# Maker_Faire_Machine_Panel4_P1_dont_use_p.net
KiCad netlist of a schematic drawn in EAGLE
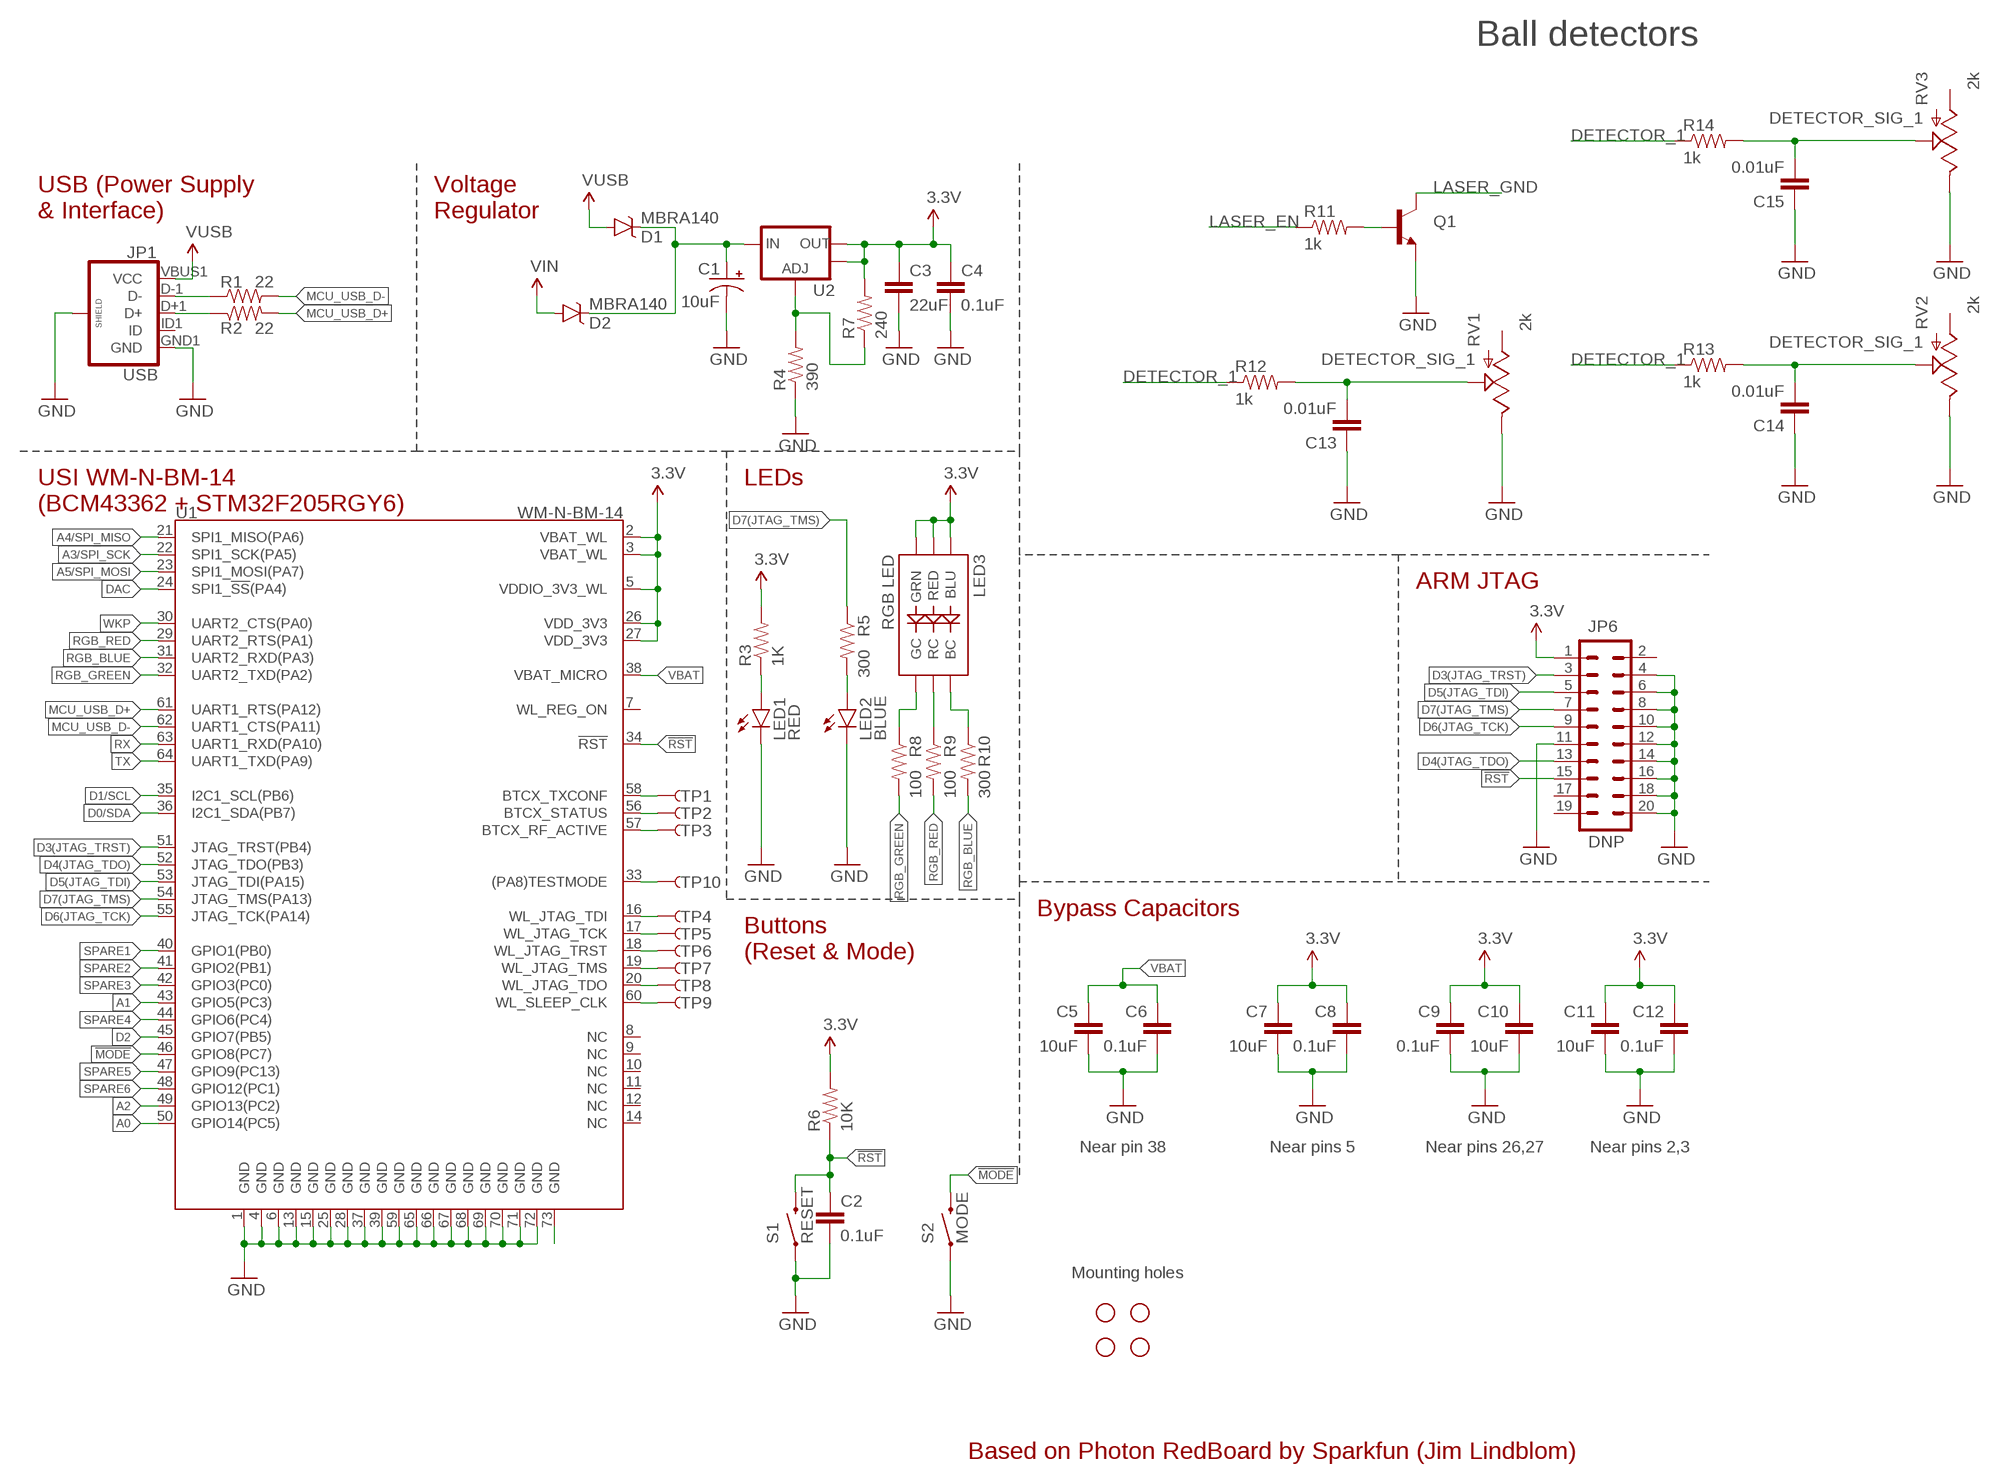
[diagram p0: schematic, sheet 1]

(export (version "E")
  (design (tool "Eeschema 10.0.6"))
  (components
    (comp (ref "C1")
      (value "10uF")
      (footprint "eagle-import:EIA3216")
      (libsource (lib "eagle-import") (part "10UF-16V-10%(TANT)"))
    )
    (comp (ref "C2")
      (value "0.1uF")
      (footprint "eagle-import:0603-CAP")
      (libsource (lib "eagle-import") (part "0.1UF-25V(+80/-20%)(0603)"))
    )
    (comp (ref "C3")
      (value "22uF")
      (footprint "eagle-import:0805")
      (libsource (lib "eagle-import") (part "22UF-6.3V-20%(0805)"))
    )
    (comp (ref "C4")
      (value "0.1uF")
      (footprint "eagle-import:0603-CAP")
      (libsource (lib "eagle-import") (part "0.1UF-25V(+80/-20%)(0603)"))
    )
    (comp (ref "C5")
      (value "10uF")
      (footprint "eagle-import:0603-CAP")
      (libsource (lib "eagle-import") (part "10UF-6.3V-20%(0603)"))
    )
    (comp (ref "C6")
      (value "0.1uF")
      (footprint "eagle-import:0603-CAP")
      (libsource (lib "eagle-import") (part "0.1UF-25V(+80/-20%)(0603)"))
    )
    (comp (ref "C7")
      (value "10uF")
      (footprint "eagle-import:0603-CAP")
      (libsource (lib "eagle-import") (part "10UF-6.3V-20%(0603)"))
    )
    (comp (ref "C8")
      (value "0.1uF")
      (footprint "eagle-import:0603-CAP")
      (libsource (lib "eagle-import") (part "0.1UF-25V(+80/-20%)(0603)"))
    )
    (comp (ref "C9")
      (value "0.1uF")
      (footprint "eagle-import:0603-CAP")
      (libsource (lib "eagle-import") (part "0.1UF-25V(+80/-20%)(0603)"))
    )
    (comp (ref "C10")
      (value "10uF")
      (footprint "eagle-import:0603-CAP")
      (libsource (lib "eagle-import") (part "10UF-6.3V-20%(0603)"))
    )
    (comp (ref "C11")
      (value "10uF")
      (footprint "eagle-import:0603-CAP")
      (libsource (lib "eagle-import") (part "10UF-6.3V-20%(0603)"))
    )
    (comp (ref "C12")
      (value "0.1uF")
      (footprint "eagle-import:0603-CAP")
      (libsource (lib "eagle-import") (part "0.1UF-25V(+80/-20%)(0603)"))
    )
    (comp (ref "C13")
      (value "0.01uF")
      (footprint "eagle-import:1206")
      (fields (field (name "PARTNO") "12065C103KAT2A"))
      (libsource (lib "eagle-import") (part "CAP1206"))
    )
    (comp (ref "C14")
      (value "0.01uF")
      (footprint "eagle-import:1206")
      (fields (field (name "PARTNO") "12065C103KAT2A"))
      (libsource (lib "eagle-import") (part "CAP1206"))
    )
    (comp (ref "C15")
      (value "0.01uF")
      (footprint "eagle-import:1206")
      (fields (field (name "PARTNO") "12065C103KAT2A"))
      (libsource (lib "eagle-import") (part "CAP1206"))
    )
    (comp (ref "D1")
      (value "MBRA140")
      (footprint "eagle-import:SMA-DIODE")
      (libsource (lib "eagle-import") (part "DIODE-SCHOTTKY-MBRA140"))
    )
    (comp (ref "D2")
      (value "MBRA140")
      (footprint "eagle-import:SMA-DIODE")
      (libsource (lib "eagle-import") (part "DIODE-SCHOTTKY-MBRA140"))
    )
    (comp (ref "JP1")
      (value "USB")
      (footprint "eagle-import:USB-B-MICRO-SMD_V03")
      (libsource (lib "eagle-import") (part "USB_MICROB_PLUGCONN-11752"))
    )
    (comp (ref "JP6")
      (value "DNP")
      (footprint "eagle-import:2X10")
      (libsource (lib "eagle-import") (part "M10X2"))
    )
    (comp (ref "LED1")
      (value "RED")
      (footprint "eagle-import:LED-1206")
      (libsource (lib "eagle-import") (part "LED-RED1206"))
    )
    (comp (ref "LED2")
      (value "BLUE")
      (footprint "eagle-import:LED-1206")
      (libsource (lib "eagle-import") (part "LED-BLUE1206"))
    )
    (comp (ref "LED3")
      (value "RGB LED")
      (footprint "eagle-import:PLCC-6-LED")
      (libsource (lib "eagle-import") (part "LED-TRICOLOR-NO-COMPLCC-6-SMD"))
    )
    (comp (ref "Q1")
      (value "TRANSISTOR_NPNSOT89")
      (footprint "eagle-import:SOT89")
      (fields (field (name "PARTNO") "PN2222ABU"))
      (libsource (lib "eagle-import") (part "TRANSISTOR_NPNSOT89"))
    )
    (comp (ref "R1")
      (value "22")
      (footprint "eagle-import:0603-RES")
      (libsource (lib "eagle-import") (part "22OHM1/10W1%(0603)"))
    )
    (comp (ref "R2")
      (value "22")
      (footprint "eagle-import:0603-RES")
      (libsource (lib "eagle-import") (part "22OHM1/10W1%(0603)"))
    )
    (comp (ref "R3")
      (value "1K")
      (footprint "eagle-import:0603-RES")
      (libsource (lib "eagle-import") (part "1KOHM-1/10W-1%(0603)"))
    )
    (comp (ref "R4")
      (value "390")
      (footprint "eagle-import:0603-RES")
      (libsource (lib "eagle-import") (part "390OHM1/10W1%(0603)"))
    )
    (comp (ref "R5")
      (value "300")
      (footprint "eagle-import:0603-RES")
      (libsource (lib "eagle-import") (part "300OHM-1/10W-1%(0603)"))
    )
    (comp (ref "R6")
      (value "10K")
      (footprint "eagle-import:0603-RES")
      (libsource (lib "eagle-import") (part "10KOHM-1/10W-1%(0603)0603"))
    )
    (comp (ref "R7")
      (value "240")
      (footprint "eagle-import:0603-RES")
      (libsource (lib "eagle-import") (part "240OHM1/10W1%(0603)"))
    )
    (comp (ref "R8")
      (value "100")
      (footprint "eagle-import:0603-RES")
      (libsource (lib "eagle-import") (part "100OHM-1/10W-1%(0603)"))
    )
    (comp (ref "R9")
      (value "100")
      (footprint "eagle-import:0603-RES")
      (libsource (lib "eagle-import") (part "100OHM-1/10W-1%(0603)"))
    )
    (comp (ref "R10")
      (value "300")
      (footprint "eagle-import:0603-RES")
      (libsource (lib "eagle-import") (part "300OHM-1/10W-1%(0603)"))
    )
    (comp (ref "R11")
      (value "1k")
      (footprint "eagle-import:1206")
      (fields (field (name "PARTNO") "ERJ-8ENF1001V"))
      (libsource (lib "eagle-import") (part "RESISTOR1206"))
    )
    (comp (ref "R12")
      (value "1k")
      (footprint "eagle-import:1206")
      (fields (field (name "PARTNO") "ERJ-8ENF1001V"))
      (libsource (lib "eagle-import") (part "RESISTOR1206"))
    )
    (comp (ref "R13")
      (value "1k")
      (footprint "eagle-import:1206")
      (fields (field (name "PARTNO") "ERJ-8ENF1001V"))
      (libsource (lib "eagle-import") (part "RESISTOR1206"))
    )
    (comp (ref "R14")
      (value "1k")
      (footprint "eagle-import:1206")
      (fields (field (name "PARTNO") "ERJ-8ENF1001V"))
      (libsource (lib "eagle-import") (part "RESISTOR1206"))
    )
    (comp (ref "RV1")
      (value "2k")
      (footprint "eagle-import:3362U")
      (fields (field (name "PARTNO") "3362U-1-202LF"))
      (libsource (lib "eagle-import") (part "POT100K_3362U"))
    )
    (comp (ref "RV2")
      (value "2k")
      (footprint "eagle-import:3362U")
      (fields (field (name "PARTNO") "3362U-1-202LF"))
      (libsource (lib "eagle-import") (part "POT100K_3362U"))
    )
    (comp (ref "RV3")
      (value "2k")
      (footprint "eagle-import:3362U")
      (fields (field (name "PARTNO") "3362U-1-202LF"))
      (libsource (lib "eagle-import") (part "POT100K_3362U"))
    )
    (comp (ref "S1")
      (value "RESET")
      (footprint "eagle-import:TACTILE-PTH")
      (libsource (lib "eagle-import") (part "SWITCH-MOMENTARY-2PTH"))
    )
    (comp (ref "S2")
      (value "MODE")
      (footprint "eagle-import:TACTILE-PTH")
      (libsource (lib "eagle-import") (part "SWITCH-MOMENTARY-2PTH"))
    )
    (comp (ref "STANDOFF1")
      (value "STAND-OFF")
      (footprint "eagle-import:STAND-OFF")
      (libsource (lib "eagle-import") (part "STAND-OFF"))
    )
    (comp (ref "STANDOFF2")
      (value "STAND-OFF")
      (footprint "eagle-import:STAND-OFF")
      (libsource (lib "eagle-import") (part "STAND-OFF"))
    )
    (comp (ref "STANDOFF3")
      (value "STAND-OFF")
      (footprint "eagle-import:STAND-OFF")
      (libsource (lib "eagle-import") (part "STAND-OFF"))
    )
    (comp (ref "STANDOFF4")
      (value "STAND-OFF")
      (footprint "eagle-import:STAND-OFF")
      (libsource (lib "eagle-import") (part "STAND-OFF"))
    )
    (comp (ref "TP1")
      (value "TEST-POINTTP_15TH_THRU")
      (footprint "eagle-import:TP_15TH")
      (libsource (lib "eagle-import") (part "TEST-POINTTP_15TH_THRU"))
    )
    (comp (ref "TP2")
      (value "TEST-POINTTP_15TH_THRU")
      (footprint "eagle-import:TP_15TH")
      (libsource (lib "eagle-import") (part "TEST-POINTTP_15TH_THRU"))
    )
    (comp (ref "TP3")
      (value "TEST-POINTTP_15TH_THRU")
      (footprint "eagle-import:TP_15TH")
      (libsource (lib "eagle-import") (part "TEST-POINTTP_15TH_THRU"))
    )
    (comp (ref "TP4")
      (value "TEST-POINTTP_15TH_THRU")
      (footprint "eagle-import:TP_15TH")
      (libsource (lib "eagle-import") (part "TEST-POINTTP_15TH_THRU"))
    )
    (comp (ref "TP5")
      (value "TEST-POINTTP_15TH_THRU")
      (footprint "eagle-import:TP_15TH")
      (libsource (lib "eagle-import") (part "TEST-POINTTP_15TH_THRU"))
    )
    (comp (ref "TP6")
      (value "TEST-POINTTP_15TH_THRU")
      (footprint "eagle-import:TP_15TH")
      (libsource (lib "eagle-import") (part "TEST-POINTTP_15TH_THRU"))
    )
    (comp (ref "TP7")
      (value "TEST-POINTTP_15TH_THRU")
      (footprint "eagle-import:TP_15TH")
      (libsource (lib "eagle-import") (part "TEST-POINTTP_15TH_THRU"))
    )
    (comp (ref "TP8")
      (value "TEST-POINTTP_15TH_THRU")
      (footprint "eagle-import:TP_15TH")
      (libsource (lib "eagle-import") (part "TEST-POINTTP_15TH_THRU"))
    )
    (comp (ref "TP9")
      (value "TEST-POINTTP_15TH_THRU")
      (footprint "eagle-import:TP_15TH")
      (libsource (lib "eagle-import") (part "TEST-POINTTP_15TH_THRU"))
    )
    (comp (ref "TP10")
      (value "TEST-POINTTP_15TH_THRU")
      (footprint "eagle-import:TP_15TH")
      (libsource (lib "eagle-import") (part "TEST-POINTTP_15TH_THRU"))
    )
    (comp (ref "U1")
      (value "WM-N-BM-14")
      (footprint "eagle-import:WM-N-BM-14")
      (libsource (lib "eagle-import") (part "WM-N-BM-14"))
    )
    (comp (ref "U2")
      (value "V_REG_LM1117SOT223")
      (footprint "eagle-import:SOT223")
      (libsource (lib "eagle-import") (part "V_REG_LM1117SOT223"))
    )
  )
  (nets
    (net (code "1") (name "/DETECTOR_1") (class "Default")
      (node (ref "R12") (pin "1") (pinfunction "1_1") (pintype "passive"))
      (node (ref "R13") (pin "1") (pinfunction "1_1") (pintype "passive"))
      (node (ref "R14") (pin "1") (pinfunction "1_1") (pintype "passive"))
    )
    (net (code "2") (name "/DETECTOR_SIG_1") (class "Default")
      (node (ref "C13") (pin "2") (pinfunction "2_2") (pintype "passive"))
      (node (ref "C14") (pin "2") (pinfunction "2_2") (pintype "passive"))
      (node (ref "C15") (pin "2") (pinfunction "2_2") (pintype "passive"))
      (node (ref "R12") (pin "2") (pinfunction "2_2") (pintype "passive"))
      (node (ref "R13") (pin "2") (pinfunction "2_2") (pintype "passive"))
      (node (ref "R14") (pin "2") (pinfunction "2_2") (pintype "passive"))
      (node (ref "RV1") (pin "P$2") (pinfunction "S_P$2") (pintype "passive"))
      (node (ref "RV2") (pin "P$2") (pinfunction "S_P$2") (pintype "passive"))
      (node (ref "RV3") (pin "P$2") (pinfunction "S_P$2") (pintype "passive"))
    )
    (net (code "3") (name "/LASER_EN") (class "Default")
      (node (ref "R11") (pin "1") (pinfunction "1_1") (pintype "passive"))
    )
    (net (code "4") (name "/LASER_GND") (class "Default")
      (node (ref "Q1") (pin "2") (pinfunction "C_2") (pintype "passive"))
    )
    (net (code "5") (name "/~{MODE}") (class "Default")
      (node (ref "S2") (pin "3") (pinfunction "2_3") (pintype "passive"))
      (node (ref "U1") (pin "46") (pinfunction "GPIO8(PC7)_46") (pintype "bidirectional"))
    )
    (net (code "6") (name "/~{RST}") (class "Default")
      (node (ref "C2") (pin "1") (pinfunction "1_1") (pintype "passive"))
      (node (ref "JP6") (pin "15") (pinfunction "15_15") (pintype "passive"))
      (node (ref "R6") (pin "1") (pinfunction "1_1") (pintype "passive"))
      (node (ref "S1") (pin "3") (pinfunction "2_3") (pintype "passive"))
      (node (ref "U1") (pin "34") (pinfunction "~{RST}_34") (pintype "bidirectional"))
    )
    (net (code "7") (name "3.3V") (class "Default")
      (node (ref "C10") (pin "1") (pinfunction "1_1") (pintype "passive"))
      (node (ref "C11") (pin "1") (pinfunction "1_1") (pintype "passive"))
      (node (ref "C12") (pin "1") (pinfunction "1_1") (pintype "passive"))
      (node (ref "C3") (pin "1") (pinfunction "1_1") (pintype "passive"))
      (node (ref "C4") (pin "1") (pinfunction "1_1") (pintype "passive"))
      (node (ref "C7") (pin "1") (pinfunction "1_1") (pintype "passive"))
      (node (ref "C8") (pin "1") (pinfunction "1_1") (pintype "passive"))
      (node (ref "C9") (pin "1") (pinfunction "1_1") (pintype "passive"))
      (node (ref "JP6") (pin "1") (pinfunction "1_1") (pintype "passive"))
      (node (ref "LED3") (pin "AB") (pinfunction "BLU_AB") (pintype "bidirectional"))
      (node (ref "LED3") (pin "AG") (pinfunction "GRN_AG") (pintype "bidirectional"))
      (node (ref "LED3") (pin "AR") (pinfunction "RED_AR") (pintype "bidirectional"))
      (node (ref "R3") (pin "2") (pinfunction "2_2") (pintype "passive"))
      (node (ref "R6") (pin "2") (pinfunction "2_2") (pintype "passive"))
      (node (ref "R7") (pin "2") (pinfunction "2_2") (pintype "passive"))
      (node (ref "U1") (pin "2") (pinfunction "VBAT_WL_2") (pintype "bidirectional"))
      (node (ref "U1") (pin "26") (pinfunction "VDD_3V3_26") (pintype "bidirectional"))
      (node (ref "U1") (pin "27") (pinfunction "VDD_3V3_27") (pintype "bidirectional"))
      (node (ref "U1") (pin "3") (pinfunction "VBAT_WL_3") (pintype "bidirectional"))
      (node (ref "U1") (pin "5") (pinfunction "VDDIO_3V3_WL_5") (pintype "bidirectional"))
      (node (ref "U2") (pin "2") (pinfunction "OUT_2") (pintype "output"))
      (node (ref "U2") (pin "4") (pinfunction "OUT_4") (pintype "output"))
    )
    (net (code "8") (name "A0") (class "Default")
      (node (ref "U1") (pin "50") (pinfunction "GPIO14(PC5)_50") (pintype "bidirectional"))
    )
    (net (code "9") (name "A1") (class "Default")
      (node (ref "U1") (pin "43") (pinfunction "GPIO5(PC3)_43") (pintype "bidirectional"))
    )
    (net (code "10") (name "A2") (class "Default")
      (node (ref "U1") (pin "49") (pinfunction "GPIO13(PC2)_49") (pintype "bidirectional"))
    )
    (net (code "11") (name "A3{slash}SPI_SCK") (class "Default")
      (node (ref "U1") (pin "22") (pinfunction "SPI1_SCK(PA5)_22") (pintype "bidirectional"))
    )
    (net (code "12") (name "A4{slash}SPI_MISO") (class "Default")
      (node (ref "U1") (pin "21") (pinfunction "SPI1_MISO(PA6)_21") (pintype "bidirectional"))
    )
    (net (code "13") (name "A5{slash}SPI_MOSI") (class "Default")
      (node (ref "U1") (pin "23") (pinfunction "SPI1_MOSI(PA7)_23") (pintype "bidirectional"))
    )
    (net (code "14") (name "D0{slash}SDA") (class "Default")
      (node (ref "U1") (pin "36") (pinfunction "I2C1_SDA(PB7)_36") (pintype "bidirectional"))
    )
    (net (code "15") (name "D1{slash}SCL") (class "Default")
      (node (ref "U1") (pin "35") (pinfunction "I2C1_SCL(PB6)_35") (pintype "bidirectional"))
    )
    (net (code "16") (name "D2") (class "Default")
      (node (ref "U1") (pin "45") (pinfunction "GPIO7(PB5)_45") (pintype "bidirectional"))
    )
    (net (code "17") (name "D3(JTAG_TRST)") (class "Default")
      (node (ref "JP6") (pin "3") (pinfunction "3_3") (pintype "passive"))
      (node (ref "U1") (pin "51") (pinfunction "JTAG_TRST(PB4)_51") (pintype "bidirectional"))
    )
    (net (code "18") (name "D4(JTAG_TDO)") (class "Default")
      (node (ref "JP6") (pin "13") (pinfunction "13_13") (pintype "passive"))
      (node (ref "U1") (pin "52") (pinfunction "JTAG_TDO(PB3)_52") (pintype "bidirectional"))
    )
    (net (code "19") (name "D5(JTAG_TDI)") (class "Default")
      (node (ref "JP6") (pin "5") (pinfunction "5_5") (pintype "passive"))
      (node (ref "U1") (pin "53") (pinfunction "JTAG_TDI(PA15)_53") (pintype "bidirectional"))
    )
    (net (code "20") (name "D6(JTAG_TCK)") (class "Default")
      (node (ref "JP6") (pin "9") (pinfunction "9_9") (pintype "passive"))
      (node (ref "U1") (pin "55") (pinfunction "JTAG_TCK(PA14)_55") (pintype "bidirectional"))
    )
    (net (code "21") (name "D7(JTAG_TMS)") (class "Default")
      (node (ref "JP6") (pin "7") (pinfunction "7_7") (pintype "passive"))
      (node (ref "R5") (pin "1") (pinfunction "1_1") (pintype "passive"))
      (node (ref "U1") (pin "54") (pinfunction "JTAG_TMS(PA13)_54") (pintype "bidirectional"))
    )
    (net (code "22") (name "DAC") (class "Default")
      (node (ref "U1") (pin "24") (pinfunction "SPI1_~{SS}(PA4)_24") (pintype "bidirectional"))
    )
    (net (code "23") (name "GND") (class "Default")
      (node (ref "C1") (pin "C") (pinfunction "-_C") (pintype "passive"))
      (node (ref "C10") (pin "2") (pinfunction "2_2") (pintype "passive"))
      (node (ref "C11") (pin "2") (pinfunction "2_2") (pintype "passive"))
      (node (ref "C12") (pin "2") (pinfunction "2_2") (pintype "passive"))
      (node (ref "C13") (pin "1") (pinfunction "1_1") (pintype "passive"))
      (node (ref "C14") (pin "1") (pinfunction "1_1") (pintype "passive"))
      (node (ref "C15") (pin "1") (pinfunction "1_1") (pintype "passive"))
      (node (ref "C2") (pin "2") (pinfunction "2_2") (pintype "passive"))
      (node (ref "C3") (pin "2") (pinfunction "2_2") (pintype "passive"))
      (node (ref "C4") (pin "2") (pinfunction "2_2") (pintype "passive"))
      (node (ref "C5") (pin "2") (pinfunction "2_2") (pintype "passive"))
      (node (ref "C6") (pin "2") (pinfunction "2_2") (pintype "passive"))
      (node (ref "C7") (pin "2") (pinfunction "2_2") (pintype "passive"))
      (node (ref "C8") (pin "2") (pinfunction "2_2") (pintype "passive"))
      (node (ref "C9") (pin "2") (pinfunction "2_2") (pintype "passive"))
      (node (ref "JP1") (pin "GND1") (pinfunction "GND_GND1") (pintype "bidirectional"))
      (node (ref "JP1") (pin "SHIELD1") (pinfunction "SHIELD_SHIELD1") (pintype "bidirectional"))
      (node (ref "JP1") (pin "SHIELD2") (pinfunction "SHIELD_SHIELD2") (pintype "bidirectional"))
      (node (ref "JP1") (pin "SHIELD3") (pinfunction "SHIELD_SHIELD3") (pintype "bidirectional"))
      (node (ref "JP6") (pin "10") (pinfunction "10_10") (pintype "passive"))
      (node (ref "JP6") (pin "11") (pinfunction "11_11") (pintype "passive"))
      (node (ref "JP6") (pin "12") (pinfunction "12_12") (pintype "passive"))
      (node (ref "JP6") (pin "14") (pinfunction "14_14") (pintype "passive"))
      (node (ref "JP6") (pin "16") (pinfunction "16_16") (pintype "passive"))
      (node (ref "JP6") (pin "18") (pinfunction "18_18") (pintype "passive"))
      (node (ref "JP6") (pin "20") (pinfunction "20_20") (pintype "passive"))
      (node (ref "JP6") (pin "4") (pinfunction "4_4") (pintype "passive"))
      (node (ref "JP6") (pin "6") (pinfunction "6_6") (pintype "passive"))
      (node (ref "JP6") (pin "8") (pinfunction "8_8") (pintype "passive"))
      (node (ref "LED1") (pin "C") (pinfunction "C_C") (pintype "passive"))
      (node (ref "LED2") (pin "C") (pinfunction "C_C") (pintype "passive"))
      (node (ref "Q1") (pin "3") (pinfunction "E_3") (pintype "passive"))
      (node (ref "R4") (pin "1") (pinfunction "1_1") (pintype "passive"))
      (node (ref "RV1") (pin "P$1") (pinfunction "E_P$1") (pintype "passive"))
      (node (ref "RV2") (pin "P$1") (pinfunction "E_P$1") (pintype "passive"))
      (node (ref "RV3") (pin "P$1") (pinfunction "E_P$1") (pintype "passive"))
      (node (ref "S1") (pin "1") (pinfunction "1_1") (pintype "passive"))
      (node (ref "S2") (pin "1") (pinfunction "1_1") (pintype "passive"))
      (node (ref "U1") (pin "1") (pinfunction "GND_1") (pintype "bidirectional"))
      (node (ref "U1") (pin "13") (pinfunction "GND_13") (pintype "bidirectional"))
      (node (ref "U1") (pin "15") (pinfunction "GND_15") (pintype "bidirectional"))
      (node (ref "U1") (pin "25") (pinfunction "GND_25") (pintype "bidirectional"))
      (node (ref "U1") (pin "28") (pinfunction "GND_28") (pintype "bidirectional"))
      (node (ref "U1") (pin "37") (pinfunction "GND_37") (pintype "bidirectional"))
      (node (ref "U1") (pin "39") (pinfunction "GND_39") (pintype "bidirectional"))
      (node (ref "U1") (pin "4") (pinfunction "GND_4") (pintype "bidirectional"))
      (node (ref "U1") (pin "59") (pinfunction "GND_59") (pintype "bidirectional"))
      (node (ref "U1") (pin "6") (pinfunction "GND_6") (pintype "bidirectional"))
      (node (ref "U1") (pin "65") (pinfunction "GND_65") (pintype "bidirectional"))
      (node (ref "U1") (pin "66") (pinfunction "GND_66") (pintype "bidirectional"))
      (node (ref "U1") (pin "67") (pinfunction "GND_67") (pintype "bidirectional"))
      (node (ref "U1") (pin "68") (pinfunction "GND_68") (pintype "bidirectional"))
      (node (ref "U1") (pin "69") (pinfunction "GND_69") (pintype "bidirectional"))
      (node (ref "U1") (pin "70") (pinfunction "GND_70") (pintype "bidirectional"))
      (node (ref "U1") (pin "71") (pinfunction "GND_71") (pintype "bidirectional"))
      (node (ref "U1") (pin "72") (pinfunction "GND_72") (pintype "bidirectional"))
    )
    (net (code "24") (name "MCU_USB_D+") (class "Default")
      (node (ref "R2") (pin "2") (pinfunction "2_2") (pintype "passive"))
      (node (ref "U1") (pin "61") (pinfunction "UART1_RTS(PA12)_61") (pintype "bidirectional"))
    )
    (net (code "25") (name "MCU_USB_D-") (class "Default")
      (node (ref "R1") (pin "2") (pinfunction "2_2") (pintype "passive"))
      (node (ref "U1") (pin "62") (pinfunction "UART1_CTS(PA11)_62") (pintype "bidirectional"))
    )
    (net (code "26") (name "Net-(C1-+)") (class "Default")
      (node (ref "C1") (pin "A") (pinfunction "+_A") (pintype "passive"))
      (node (ref "D1") (pin "C") (pinfunction "C_C") (pintype "passive"))
      (node (ref "D2") (pin "C") (pinfunction "C_C") (pintype "passive"))
      (node (ref "U2") (pin "3") (pinfunction "IN_3") (pintype "input"))
    )
    (net (code "27") (name "Net-(JP1-D+)") (class "Default")
      (node (ref "JP1") (pin "D+1") (pinfunction "D+_D+1") (pintype "bidirectional"))
      (node (ref "R2") (pin "1") (pinfunction "1_1") (pintype "passive"))
    )
    (net (code "28") (name "Net-(JP1-D-)") (class "Default")
      (node (ref "JP1") (pin "D-1") (pinfunction "D-_D-1") (pintype "bidirectional"))
      (node (ref "R1") (pin "1") (pinfunction "1_1") (pintype "passive"))
    )
    (net (code "29") (name "Net-(LED1-PadA)") (class "Default")
      (node (ref "LED1") (pin "A") (pinfunction "A_A") (pintype "passive"))
      (node (ref "R3") (pin "1") (pinfunction "1_1") (pintype "passive"))
    )
    (net (code "30") (name "Net-(LED2-PadA)") (class "Default")
      (node (ref "LED2") (pin "A") (pinfunction "A_A") (pintype "passive"))
      (node (ref "R5") (pin "2") (pinfunction "2_2") (pintype "passive"))
    )
    (net (code "31") (name "Net-(LED3-BC)") (class "Default")
      (node (ref "LED3") (pin "CB") (pinfunction "BC_CB") (pintype "bidirectional"))
      (node (ref "R10") (pin "1") (pinfunction "1_1") (pintype "passive"))
    )
    (net (code "32") (name "Net-(LED3-GC)") (class "Default")
      (node (ref "LED3") (pin "CG") (pinfunction "GC_CG") (pintype "bidirectional"))
      (node (ref "R8") (pin "1") (pinfunction "1_1") (pintype "passive"))
    )
    (net (code "33") (name "Net-(LED3-RC)") (class "Default")
      (node (ref "LED3") (pin "CR") (pinfunction "RC_CR") (pintype "bidirectional"))
      (node (ref "R9") (pin "1") (pinfunction "1_1") (pintype "passive"))
    )
    (net (code "34") (name "Net-(Q1-B)") (class "Default")
      (node (ref "Q1") (pin "1") (pinfunction "B_1") (pintype "passive"))
      (node (ref "R11") (pin "2") (pinfunction "2_2") (pintype "passive"))
    )
    (net (code "35") (name "Net-(TP1-1)") (class "Default")
      (node (ref "TP1") (pin "P$1") (pinfunction "1_P$1") (pintype "bidirectional"))
      (node (ref "U1") (pin "58") (pinfunction "BTCX_TXCONF_58") (pintype "bidirectional"))
    )
    (net (code "36") (name "Net-(TP2-1)") (class "Default")
      (node (ref "TP2") (pin "P$1") (pinfunction "1_P$1") (pintype "bidirectional"))
      (node (ref "U1") (pin "56") (pinfunction "BTCX_STATUS_56") (pintype "bidirectional"))
    )
    (net (code "37") (name "Net-(TP3-1)") (class "Default")
      (node (ref "TP3") (pin "P$1") (pinfunction "1_P$1") (pintype "bidirectional"))
      (node (ref "U1") (pin "57") (pinfunction "BTCX_RF_ACTIVE_57") (pintype "bidirectional"))
    )
    (net (code "38") (name "Net-(TP4-1)") (class "Default")
      (node (ref "TP4") (pin "P$1") (pinfunction "1_P$1") (pintype "bidirectional"))
      (node (ref "U1") (pin "16") (pinfunction "WL_JTAG_TDI_16") (pintype "bidirectional"))
    )
    (net (code "39") (name "Net-(TP5-1)") (class "Default")
      (node (ref "TP5") (pin "P$1") (pinfunction "1_P$1") (pintype "bidirectional"))
      (node (ref "U1") (pin "17") (pinfunction "WL_JTAG_TCK_17") (pintype "bidirectional"))
    )
    (net (code "40") (name "Net-(TP6-1)") (class "Default")
      (node (ref "TP6") (pin "P$1") (pinfunction "1_P$1") (pintype "bidirectional"))
      (node (ref "U1") (pin "18") (pinfunction "WL_JTAG_TRST_18") (pintype "bidirectional"))
    )
    (net (code "41") (name "Net-(TP7-1)") (class "Default")
      (node (ref "TP7") (pin "P$1") (pinfunction "1_P$1") (pintype "bidirectional"))
      (node (ref "U1") (pin "19") (pinfunction "WL_JTAG_TMS_19") (pintype "bidirectional"))
    )
    (net (code "42") (name "Net-(TP8-1)") (class "Default")
      (node (ref "TP8") (pin "P$1") (pinfunction "1_P$1") (pintype "bidirectional"))
      (node (ref "U1") (pin "20") (pinfunction "WL_JTAG_TDO_20") (pintype "bidirectional"))
    )
    (net (code "43") (name "Net-(TP9-1)") (class "Default")
      (node (ref "TP9") (pin "P$1") (pinfunction "1_P$1") (pintype "bidirectional"))
      (node (ref "U1") (pin "60") (pinfunction "WL_SLEEP_CLK_60") (pintype "bidirectional"))
    )
    (net (code "44") (name "Net-(TP10-1)") (class "Default")
      (node (ref "TP10") (pin "P$1") (pinfunction "1_P$1") (pintype "bidirectional"))
      (node (ref "U1") (pin "33") (pinfunction "(PA8)TESTMODE_33") (pintype "bidirectional"))
    )
    (net (code "45") (name "Net-(U2-ADJ)") (class "Default")
      (node (ref "R4") (pin "2") (pinfunction "2_2") (pintype "passive"))
      (node (ref "R7") (pin "1") (pinfunction "1_1") (pintype "passive"))
      (node (ref "U2") (pin "1") (pinfunction "ADJ_1") (pintype "input"))
    )
    (net (code "46") (name "RGB_BLUE") (class "Default")
      (node (ref "R10") (pin "2") (pinfunction "2_2") (pintype "passive"))
      (node (ref "U1") (pin "31") (pinfunction "UART2_RXD(PA3)_31") (pintype "bidirectional"))
    )
    (net (code "47") (name "RGB_GREEN") (class "Default")
      (node (ref "R8") (pin "2") (pinfunction "2_2") (pintype "passive"))
      (node (ref "U1") (pin "32") (pinfunction "UART2_TXD(PA2)_32") (pintype "bidirectional"))
    )
    (net (code "48") (name "RGB_RED") (class "Default")
      (node (ref "R9") (pin "2") (pinfunction "2_2") (pintype "passive"))
      (node (ref "U1") (pin "29") (pinfunction "UART2_RTS(PA1)_29") (pintype "bidirectional"))
    )
    (net (code "49") (name "RX") (class "Default")
      (node (ref "U1") (pin "63") (pinfunction "UART1_RXD(PA10)_63") (pintype "bidirectional"))
    )
    (net (code "50") (name "SPARE1") (class "Default")
      (node (ref "U1") (pin "40") (pinfunction "GPIO1(PB0)_40") (pintype "bidirectional"))
    )
    (net (code "51") (name "SPARE2") (class "Default")
      (node (ref "U1") (pin "41") (pinfunction "GPIO2(PB1)_41") (pintype "bidirectional"))
    )
    (net (code "52") (name "SPARE3") (class "Default")
      (node (ref "U1") (pin "42") (pinfunction "GPIO3(PC0)_42") (pintype "bidirectional"))
    )
    (net (code "53") (name "SPARE4") (class "Default")
      (node (ref "U1") (pin "44") (pinfunction "GPIO6(PC4)_44") (pintype "bidirectional"))
    )
    (net (code "54") (name "SPARE5") (class "Default")
      (node (ref "U1") (pin "47") (pinfunction "GPIO9(PC13)_47") (pintype "bidirectional"))
    )
    (net (code "55") (name "SPARE6") (class "Default")
      (node (ref "U1") (pin "48") (pinfunction "GPIO12(PC1)_48") (pintype "bidirectional"))
    )
    (net (code "56") (name "TX") (class "Default")
      (node (ref "U1") (pin "64") (pinfunction "UART1_TXD(PA9)_64") (pintype "bidirectional"))
    )
    (net (code "57") (name "VBAT") (class "Default")
      (node (ref "C5") (pin "1") (pinfunction "1_1") (pintype "passive"))
      (node (ref "C6") (pin "1") (pinfunction "1_1") (pintype "passive"))
      (node (ref "U1") (pin "38") (pinfunction "VBAT_MICRO_38") (pintype "bidirectional"))
    )
    (net (code "58") (name "VIN") (class "Default")
      (node (ref "D2") (pin "A") (pinfunction "A_A") (pintype "passive"))
    )
    (net (code "59") (name "VUSB") (class "Default")
      (node (ref "D1") (pin "A") (pinfunction "A_A") (pintype "passive"))
      (node (ref "JP1") (pin "VBUS1") (pinfunction "VCC_VBUS1") (pintype "bidirectional"))
    )
    (net (code "60") (name "WKP") (class "Default")
      (node (ref "U1") (pin "30") (pinfunction "UART2_CTS(PA0)_30") (pintype "bidirectional"))
    )
    (net (code "61") (name "unconnected-(JP1-ID-PadID1)") (class "Default")
      (node (ref "JP1") (pin "ID1") (pinfunction "ID_ID1") (pintype "bidirectional"))
    )
    (net (code "62") (name "unconnected-(JP6-Pad2)") (class "Default")
      (node (ref "JP6") (pin "2") (pinfunction "2_2") (pintype "passive"))
    )
    (net (code "63") (name "unconnected-(JP6-Pad17)") (class "Default")
      (node (ref "JP6") (pin "17") (pinfunction "17_17") (pintype "passive"))
    )
    (net (code "64") (name "unconnected-(JP6-Pad19)") (class "Default")
      (node (ref "JP6") (pin "19") (pinfunction "19_19") (pintype "passive"))
    )
    (net (code "65") (name "unconnected-(RV1-A-PadP$3)") (class "Default")
      (node (ref "RV1") (pin "P$3") (pinfunction "A_P$3") (pintype "passive"))
    )
    (net (code "66") (name "unconnected-(RV2-A-PadP$3)") (class "Default")
      (node (ref "RV2") (pin "P$3") (pinfunction "A_P$3") (pintype "passive"))
    )
    (net (code "67") (name "unconnected-(RV3-A-PadP$3)") (class "Default")
      (node (ref "RV3") (pin "P$3") (pinfunction "A_P$3") (pintype "passive"))
    )
    (net (code "68") (name "unconnected-(U1-GND-Pad73)") (class "Default")
      (node (ref "U1") (pin "73") (pinfunction "GND_73") (pintype "bidirectional"))
    )
    (net (code "69") (name "unconnected-(U1-NC-Pad8)") (class "Default")
      (node (ref "U1") (pin "8") (pinfunction "NC_8") (pintype "bidirectional"))
    )
    (net (code "70") (name "unconnected-(U1-NC-Pad9)") (class "Default")
      (node (ref "U1") (pin "9") (pinfunction "NC_9") (pintype "bidirectional"))
    )
    (net (code "71") (name "unconnected-(U1-NC-Pad10)") (class "Default")
      (node (ref "U1") (pin "10") (pinfunction "NC_10") (pintype "bidirectional"))
    )
    (net (code "72") (name "unconnected-(U1-NC-Pad11)") (class "Default")
      (node (ref "U1") (pin "11") (pinfunction "NC_11") (pintype "bidirectional"))
    )
    (net (code "73") (name "unconnected-(U1-NC-Pad12)") (class "Default")
      (node (ref "U1") (pin "12") (pinfunction "NC_12") (pintype "bidirectional"))
    )
    (net (code "74") (name "unconnected-(U1-NC-Pad14)") (class "Default")
      (node (ref "U1") (pin "14") (pinfunction "NC_14") (pintype "bidirectional"))
    )
    (net (code "75") (name "unconnected-(U1-WL_REG_ON-Pad7)") (class "Default")
      (node (ref "U1") (pin "7") (pinfunction "WL_REG_ON_7") (pintype "bidirectional"))
    )
  )
)
